# ECG_v2_2.net
KiCad netlist of a schematic drawn in EAGLE
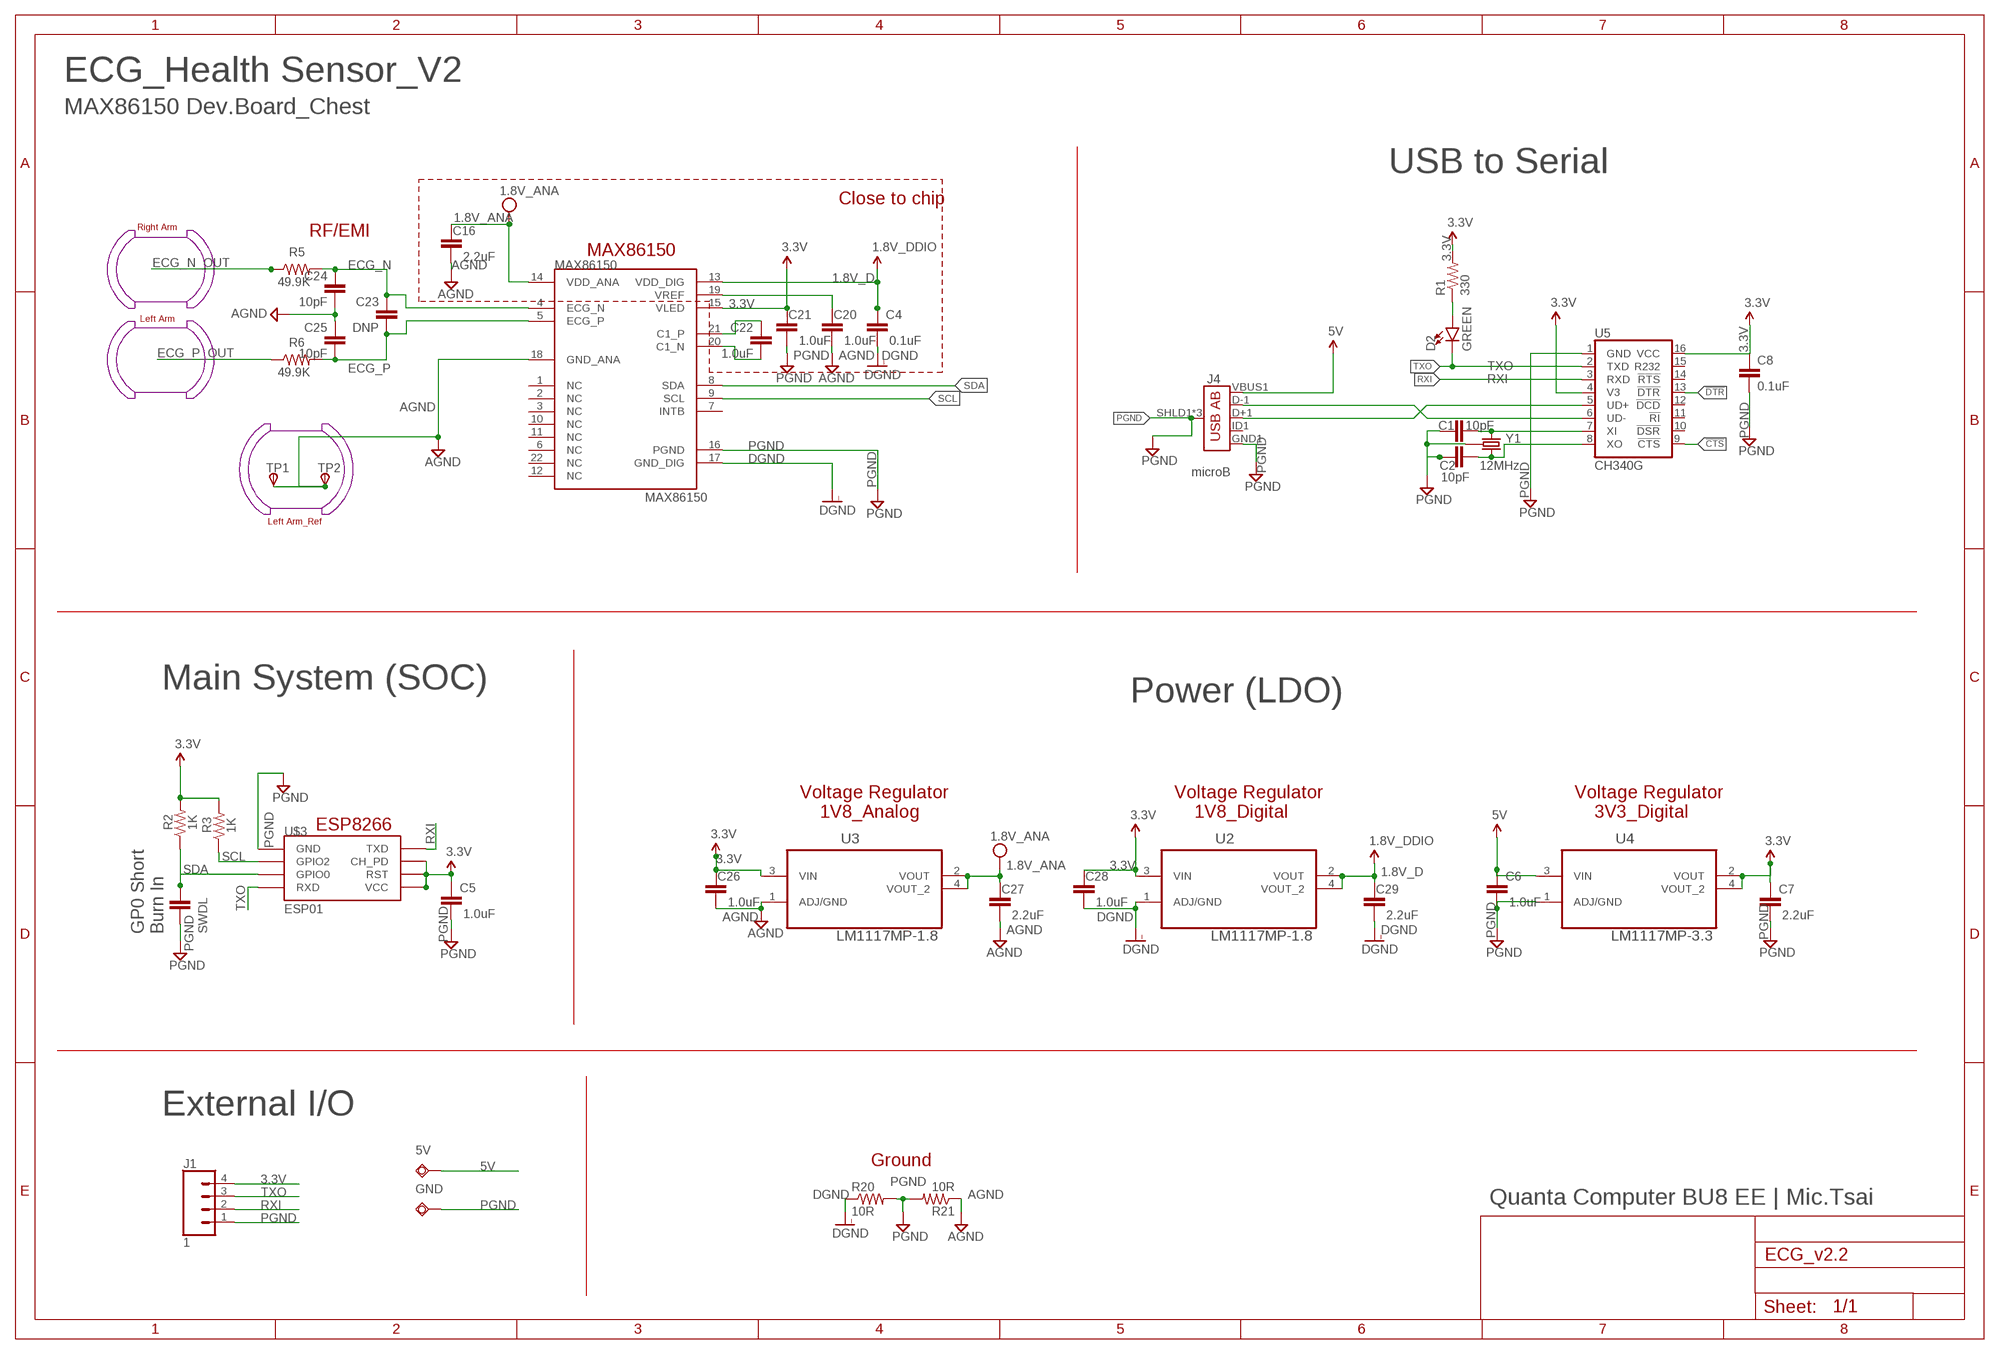
[diagram p0: schematic, sheet 1]

(export (version "E")
  (design (tool "Eeschema 10.0.6"))
  (components
    (comp (ref "5V")
      (value "TPSQTP20R")
      (footprint "eagle-import:TP20R")
      (libsource (lib "eagle-import") (part "TPSQTP20R"))
    )
    (comp (ref "C1")
      (value "10pF")
      (footprint "eagle-import:0603-CAP")
      (libsource (lib "eagle-import") (part "10PF-50V-5%(0603)"))
    )
    (comp (ref "C2")
      (value "10pF")
      (footprint "eagle-import:0603-CAP")
      (libsource (lib "eagle-import") (part "10PF-50V-5%(0603)"))
    )
    (comp (ref "C4")
      (value "0.1uF")
      (footprint "eagle-import:0805")
      (libsource (lib "eagle-import") (part "1.0UF-0805-25V-10%"))
    )
    (comp (ref "C5")
      (value "1.0uF")
      (footprint "eagle-import:0805")
      (libsource (lib "eagle-import") (part "1.0UF-0805-25V-10%"))
    )
    (comp (ref "C6")
      (value "1.0uF")
      (footprint "eagle-import:0805")
      (libsource (lib "eagle-import") (part "1.0UF-0805-25V-10%"))
    )
    (comp (ref "C7")
      (value "2.2uF")
      (footprint "eagle-import:0805")
      (libsource (lib "eagle-import") (part "1.0UF-0805-25V-10%"))
    )
    (comp (ref "C8")
      (value "0.1uF")
      (footprint "eagle-import:0603-CAP")
      (libsource (lib "eagle-import") (part "0.1UF-25V(+80/-20%)(0603)"))
    )
    (comp (ref "C16")
      (value "2.2uF")
      (footprint "eagle-import:0805")
      (libsource (lib "eagle-import") (part "1.0UF-0805-25V-10%"))
    )
    (comp (ref "C20")
      (value "1.0uF")
      (footprint "eagle-import:0805")
      (libsource (lib "eagle-import") (part "1.0UF-0805-25V-10%"))
    )
    (comp (ref "C21")
      (value "1.0uF")
      (footprint "eagle-import:0805")
      (libsource (lib "eagle-import") (part "1.0UF-0805-25V-10%"))
    )
    (comp (ref "C22")
      (value "1.0uF")
      (footprint "eagle-import:0805")
      (libsource (lib "eagle-import") (part "1.0UF-0805-25V-10%"))
    )
    (comp (ref "C23")
      (value "DNP")
      (footprint "eagle-import:0402")
      (libsource (lib "eagle-import") (part "1.0UF-0402-16V-10%"))
    )
    (comp (ref "C24")
      (value "10pF")
      (footprint "eagle-import:0402")
      (libsource (lib "eagle-import") (part "1.0UF-0402-16V-10%"))
    )
    (comp (ref "C25")
      (value "10pF")
      (footprint "eagle-import:0402")
      (libsource (lib "eagle-import") (part "1.0UF-0402-16V-10%"))
    )
    (comp (ref "C26")
      (value "1.0uF")
      (footprint "eagle-import:0805")
      (libsource (lib "eagle-import") (part "1.0UF-0805-25V-10%"))
    )
    (comp (ref "C27")
      (value "2.2uF")
      (footprint "eagle-import:0805")
      (libsource (lib "eagle-import") (part "1.0UF-0805-25V-10%"))
    )
    (comp (ref "C28")
      (value "1.0uF")
      (footprint "eagle-import:0805")
      (libsource (lib "eagle-import") (part "1.0UF-0805-25V-10%"))
    )
    (comp (ref "C29")
      (value "2.2uF")
      (footprint "eagle-import:0805")
      (libsource (lib "eagle-import") (part "1.0UF-0805-25V-10%"))
    )
    (comp (ref "D2")
      (value "GREEN")
      (footprint "eagle-import:LED-0603")
      (libsource (lib "eagle-import") (part "LED-GREEN0603"))
    )
    (comp (ref "GND")
      (value "TPSQTP20R")
      (footprint "eagle-import:TP20R")
      (libsource (lib "eagle-import") (part "TPSQTP20R"))
    )
    (comp (ref "J1")
      (value "1")
      (footprint "eagle-import:1X04")
      (libsource (lib "eagle-import") (part "CONN_04"))
    )
    (comp (ref "J4")
      (value "microB")
      (footprint "eagle-import:USB-AB-MICRO-SMD")
      (libsource (lib "eagle-import") (part "USB_AB_SMT"))
    )
    (comp (ref "MAX86150")
      (value "MAX86150")
      (footprint "eagle-import:MAX86150")
      (libsource (lib "eagle-import") (part "MAX86150"))
    )
    (comp (ref "R1")
      (value "330")
      (footprint "eagle-import:0603-RES")
      (libsource (lib "eagle-import") (part "330OHM1/10W1%(0603)"))
    )
    (comp (ref "R2")
      (value "1K")
      (footprint "eagle-import:0805")
      (libsource (lib "eagle-import") (part "RESISTOR0805-RES"))
    )
    (comp (ref "R3")
      (value "1K")
      (footprint "eagle-import:0805")
      (libsource (lib "eagle-import") (part "RESISTOR0805-RES"))
    )
    (comp (ref "R5")
      (value "49.9K")
      (footprint "eagle-import:0805")
      (libsource (lib "eagle-import") (part "RESISTOR0805-RES"))
    )
    (comp (ref "R6")
      (value "49.9K")
      (footprint "eagle-import:0805")
      (libsource (lib "eagle-import") (part "RESISTOR0805-RES"))
    )
    (comp (ref "R20")
      (value "10R")
      (footprint "eagle-import:0805")
      (libsource (lib "eagle-import") (part "RESISTOR0805-RES"))
    )
    (comp (ref "R21")
      (value "10R")
      (footprint "eagle-import:0805")
      (libsource (lib "eagle-import") (part "RESISTOR0805-RES"))
    )
    (comp (ref "SWDL")
      (value "10pF")
      (footprint "eagle-import:0402")
      (libsource (lib "eagle-import") (part "1.0UF-0402-16V-10%"))
    )
    (comp (ref "TP1")
      (value "TPSB1,27")
      (footprint "eagle-import:B1,27")
      (libsource (lib "eagle-import") (part "TPSB1,27"))
    )
    (comp (ref "TP2")
      (value "TPSB1,27")
      (footprint "eagle-import:B1,27")
      (libsource (lib "eagle-import") (part "TPSB1,27"))
    )
    (comp (ref "U$3")
      (value "ESP01")
      (footprint "eagle-import:ESP01")
      (libsource (lib "eagle-import") (part "ESP01"))
    )
    (comp (ref "U2")
      (value "LM1117MP-1.8")
      (footprint "eagle-import:SOT230P696X180-4N")
      (fields (field (name "MF") "Texas Instruments") (field (name "MP") "LM1117MP-1.8/NOPB"))
      (libsource (lib "eagle-import") (part "LM1117MP-1.8"))
    )
    (comp (ref "U3")
      (value "LM1117MP-1.8")
      (footprint "eagle-import:SOT230P696X180-4N")
      (fields (field (name "MF") "Texas Instruments") (field (name "MP") "LM1117MP-1.8/NOPB"))
      (libsource (lib "eagle-import") (part "LM1117MP-1.8"))
    )
    (comp (ref "U4")
      (value "LM1117MP-3.3")
      (footprint "eagle-import:SOT230P696X180-4N")
      (fields (field (name "MF") "Texas Instruments") (field (name "MP") "LM1117MP-1.8/NOPB"))
      (libsource (lib "eagle-import") (part "LM1117MP-3.3"))
    )
    (comp (ref "U5")
      (value "CH340G")
      (footprint "eagle-import:SO016")
      (libsource (lib "eagle-import") (part "CH340GSMD"))
    )
    (comp (ref "Y1")
      (value "12MHz")
      (footprint "eagle-import:CRYSTAL-SMD-3.2X2.5")
      (libsource (lib "eagle-import") (part "CRYSTAL-GROUNDED3.2X2.5"))
    )
  )
  (nets
    (net (code "1") (name "/ECG_N") (class "Default")
      (node (ref "C23") (pin "1") (pinfunction "1_1") (pintype "passive"))
      (node (ref "C24") (pin "1") (pinfunction "1_1") (pintype "passive"))
      (node (ref "MAX86150") (pin "4") (pinfunction "ECG_N_4") (pintype "bidirectional"))
      (node (ref "R5") (pin "2") (pinfunction "2_2") (pintype "passive"))
    )
    (net (code "2") (name "/ECG_N_OUT") (class "Default")
      (node (ref "R5") (pin "1") (pinfunction "1_1") (pintype "passive"))
    )
    (net (code "3") (name "/ECG_P") (class "Default")
      (node (ref "C23") (pin "2") (pinfunction "2_2") (pintype "passive"))
      (node (ref "C25") (pin "2") (pinfunction "2_2") (pintype "passive"))
      (node (ref "MAX86150") (pin "5") (pinfunction "ECG_P_5") (pintype "bidirectional"))
      (node (ref "R6") (pin "2") (pinfunction "2_2") (pintype "passive"))
    )
    (net (code "4") (name "/ECG_P_OUT") (class "Default")
      (node (ref "R6") (pin "1") (pinfunction "1_1") (pintype "passive"))
    )
    (net (code "5") (name "/~{CTS}") (class "Default")
      (node (ref "U5") (pin "9") (pinfunction "~{CTS}_9") (pintype "bidirectional"))
    )
    (net (code "6") (name "/~{DTR}") (class "Default")
      (node (ref "U5") (pin "13") (pinfunction "~{DTR}_13") (pintype "bidirectional"))
    )
    (net (code "7") (name "1.8V_ANA") (class "Default")
      (node (ref "C16") (pin "1") (pinfunction "1_1") (pintype "passive"))
      (node (ref "C27") (pin "1") (pinfunction "1_1") (pintype "passive"))
      (node (ref "MAX86150") (pin "14") (pinfunction "VDD_ANA_14") (pintype "bidirectional"))
      (node (ref "U3") (pin "2") (pinfunction "VOUT_2") (pintype "output"))
      (node (ref "U3") (pin "4") (pinfunction "VOUT_2_4") (pintype "output"))
    )
    (net (code "8") (name "1.8V_DDIO") (class "Default")
      (node (ref "C29") (pin "1") (pinfunction "1_1") (pintype "passive"))
      (node (ref "C4") (pin "1") (pinfunction "1_1") (pintype "passive"))
      (node (ref "MAX86150") (pin "13") (pinfunction "VDD_DIG_13") (pintype "bidirectional"))
      (node (ref "U2") (pin "2") (pinfunction "VOUT_2") (pintype "output"))
      (node (ref "U2") (pin "4") (pinfunction "VOUT_2_4") (pintype "output"))
    )
    (net (code "9") (name "3.3V") (class "Default")
      (node (ref "C21") (pin "1") (pinfunction "1_1") (pintype "passive"))
      (node (ref "C26") (pin "1") (pinfunction "1_1") (pintype "passive"))
      (node (ref "C28") (pin "1") (pinfunction "1_1") (pintype "passive"))
      (node (ref "C5") (pin "1") (pinfunction "1_1") (pintype "passive"))
      (node (ref "C7") (pin "1") (pinfunction "1_1") (pintype "passive"))
      (node (ref "C8") (pin "1") (pinfunction "1_1") (pintype "passive"))
      (node (ref "J1") (pin "4") (pinfunction "4_4") (pintype "passive"))
      (node (ref "MAX86150") (pin "15") (pinfunction "VLED_15") (pintype "bidirectional"))
      (node (ref "R1") (pin "2") (pinfunction "2_2") (pintype "passive"))
      (node (ref "R2") (pin "2") (pinfunction "2_2") (pintype "passive"))
      (node (ref "R3") (pin "2") (pinfunction "2_2") (pintype "passive"))
      (node (ref "U$3") (pin "CH_PD") (pinfunction "CH_PD_CH_PD") (pintype "bidirectional"))
      (node (ref "U$3") (pin "RST") (pinfunction "RST_RST") (pintype "bidirectional"))
      (node (ref "U$3") (pin "VCC") (pinfunction "VCC_VCC") (pintype "bidirectional"))
      (node (ref "U2") (pin "3") (pinfunction "VIN_3") (pintype "input"))
      (node (ref "U3") (pin "3") (pinfunction "VIN_3") (pintype "input"))
      (node (ref "U4") (pin "2") (pinfunction "VOUT_2") (pintype "output"))
      (node (ref "U4") (pin "4") (pinfunction "VOUT_2_4") (pintype "output"))
      (node (ref "U5") (pin "16") (pinfunction "VCC_16") (pintype "bidirectional"))
      (node (ref "U5") (pin "4") (pinfunction "V3_4") (pintype "bidirectional"))
    )
    (net (code "10") (name "5V") (class "Default")
      (node (ref "5V") (pin "TP") (pinfunction "TP_TP") (pintype "input"))
      (node (ref "C6") (pin "1") (pinfunction "1_1") (pintype "passive"))
      (node (ref "J4") (pin "VBUS1") (pinfunction "VBUS_VBUS1") (pintype "power_in"))
      (node (ref "U4") (pin "3") (pinfunction "VIN_3") (pintype "input"))
    )
    (net (code "11") (name "AGND") (class "Default")
      (node (ref "C16") (pin "2") (pinfunction "2_2") (pintype "passive"))
      (node (ref "C20") (pin "2") (pinfunction "2_2") (pintype "passive"))
      (node (ref "C24") (pin "2") (pinfunction "2_2") (pintype "passive"))
      (node (ref "C25") (pin "1") (pinfunction "1_1") (pintype "passive"))
      (node (ref "C26") (pin "2") (pinfunction "2_2") (pintype "passive"))
      (node (ref "C27") (pin "2") (pinfunction "2_2") (pintype "passive"))
      (node (ref "MAX86150") (pin "18") (pinfunction "GND_ANA_18") (pintype "bidirectional"))
      (node (ref "R21") (pin "1") (pinfunction "1_1") (pintype "passive"))
      (node (ref "TP1") (pin "PP") (pinfunction "PP_PP") (pintype "input"))
      (node (ref "TP2") (pin "PP") (pinfunction "PP_PP") (pintype "input"))
      (node (ref "U3") (pin "1") (pinfunction "ADJ/GND_1") (pintype "passive"))
    )
    (net (code "12") (name "DGND") (class "Default")
      (node (ref "C28") (pin "2") (pinfunction "2_2") (pintype "passive"))
      (node (ref "C29") (pin "2") (pinfunction "2_2") (pintype "passive"))
      (node (ref "C4") (pin "2") (pinfunction "2_2") (pintype "passive"))
      (node (ref "MAX86150") (pin "17") (pinfunction "GND_DIG_17") (pintype "bidirectional"))
      (node (ref "R20") (pin "1") (pinfunction "1_1") (pintype "passive"))
      (node (ref "U2") (pin "1") (pinfunction "ADJ/GND_1") (pintype "passive"))
    )
    (net (code "13") (name "Net-(D2-PadA)") (class "Default")
      (node (ref "D2") (pin "A") (pinfunction "A_A") (pintype "passive"))
      (node (ref "R1") (pin "1") (pinfunction "1_1") (pintype "passive"))
    )
    (net (code "14") (name "Net-(J4-D+)") (class "Default")
      (node (ref "J4") (pin "D+1") (pinfunction "D+_D+1") (pintype "bidirectional"))
      (node (ref "U5") (pin "5") (pinfunction "UD+_5") (pintype "bidirectional"))
    )
    (net (code "15") (name "Net-(J4-D-)") (class "Default")
      (node (ref "J4") (pin "D-1") (pinfunction "D-_D-1") (pintype "bidirectional"))
      (node (ref "U5") (pin "6") (pinfunction "UD-_6") (pintype "bidirectional"))
    )
    (net (code "16") (name "Net-(MAX86150-C1_N)") (class "Default")
      (node (ref "C22") (pin "2") (pinfunction "2_2") (pintype "passive"))
      (node (ref "MAX86150") (pin "20") (pinfunction "C1_N_20") (pintype "bidirectional"))
    )
    (net (code "17") (name "Net-(MAX86150-C1_P)") (class "Default")
      (node (ref "C22") (pin "1") (pinfunction "1_1") (pintype "passive"))
      (node (ref "MAX86150") (pin "21") (pinfunction "C1_P_21") (pintype "bidirectional"))
    )
    (net (code "18") (name "Net-(MAX86150-VREF)") (class "Default")
      (node (ref "C20") (pin "1") (pinfunction "1_1") (pintype "passive"))
      (node (ref "MAX86150") (pin "19") (pinfunction "VREF_19") (pintype "bidirectional"))
    )
    (net (code "19") (name "Net-(U5-XI)") (class "Default")
      (node (ref "C1") (pin "2") (pinfunction "2_2") (pintype "passive"))
      (node (ref "U5") (pin "7") (pinfunction "XI_7") (pintype "bidirectional"))
      (node (ref "Y1") (pin "1") (pinfunction "1_1") (pintype "passive"))
    )
    (net (code "20") (name "Net-(U5-XO)") (class "Default")
      (node (ref "C2") (pin "2") (pinfunction "2_2") (pintype "passive"))
      (node (ref "U5") (pin "8") (pinfunction "XO_8") (pintype "bidirectional"))
      (node (ref "Y1") (pin "3") (pinfunction "2_3") (pintype "passive"))
    )
    (net (code "21") (name "PGND") (class "Default")
      (node (ref "C1") (pin "1") (pinfunction "1_1") (pintype "passive"))
      (node (ref "C2") (pin "1") (pinfunction "1_1") (pintype "passive"))
      (node (ref "C21") (pin "2") (pinfunction "2_2") (pintype "passive"))
      (node (ref "C5") (pin "2") (pinfunction "2_2") (pintype "passive"))
      (node (ref "C6") (pin "2") (pinfunction "2_2") (pintype "passive"))
      (node (ref "C7") (pin "2") (pinfunction "2_2") (pintype "passive"))
      (node (ref "C8") (pin "2") (pinfunction "2_2") (pintype "passive"))
      (node (ref "GND") (pin "TP") (pinfunction "TP_TP") (pintype "input"))
      (node (ref "J1") (pin "1") (pinfunction "1_1") (pintype "passive"))
      (node (ref "J4") (pin "GND1") (pinfunction "GND_GND1") (pintype "power_in"))
      (node (ref "J4") (pin "SHLD1") (pinfunction "SHIELD_SHLD1") (pintype "bidirectional"))
      (node (ref "J4") (pin "SHLD2") (pinfunction "SHIELD_SHLD2") (pintype "bidirectional"))
      (node (ref "J4") (pin "SHLD3") (pinfunction "SHIELD_SHLD3") (pintype "bidirectional"))
      (node (ref "MAX86150") (pin "16") (pinfunction "PGND_16") (pintype "bidirectional"))
      (node (ref "R20") (pin "2") (pinfunction "2_2") (pintype "passive"))
      (node (ref "R21") (pin "2") (pinfunction "2_2") (pintype "passive"))
      (node (ref "SWDL") (pin "2") (pinfunction "2_2") (pintype "passive"))
      (node (ref "U$3") (pin "GND") (pinfunction "GND_GND") (pintype "bidirectional"))
      (node (ref "U4") (pin "1") (pinfunction "ADJ/GND_1") (pintype "passive"))
      (node (ref "U5") (pin "1") (pinfunction "GND_1") (pintype "bidirectional"))
      (node (ref "Y1") (pin "2") (pinfunction "GND_2") (pintype "passive"))
      (node (ref "Y1") (pin "4") (pinfunction "GND_4") (pintype "passive"))
    )
    (net (code "22") (name "RXI") (class "Default")
      (node (ref "J1") (pin "2") (pinfunction "2_2") (pintype "passive"))
      (node (ref "U$3") (pin "TX") (pinfunction "TXD_TX") (pintype "bidirectional"))
      (node (ref "U5") (pin "3") (pinfunction "RXD_3") (pintype "bidirectional"))
    )
    (net (code "23") (name "SCL") (class "Default")
      (node (ref "MAX86150") (pin "9") (pinfunction "SCL_9") (pintype "bidirectional"))
      (node (ref "R3") (pin "1") (pinfunction "1_1") (pintype "passive"))
      (node (ref "U$3") (pin "GPIO2") (pinfunction "GPIO2_GPIO2") (pintype "bidirectional"))
    )
    (net (code "24") (name "SDA") (class "Default")
      (node (ref "MAX86150") (pin "8") (pinfunction "SDA_8") (pintype "bidirectional"))
      (node (ref "R2") (pin "1") (pinfunction "1_1") (pintype "passive"))
      (node (ref "SWDL") (pin "1") (pinfunction "1_1") (pintype "passive"))
      (node (ref "U$3") (pin "GPIO0") (pinfunction "GPIO0_GPIO0") (pintype "bidirectional"))
    )
    (net (code "25") (name "TXO") (class "Default")
      (node (ref "D2") (pin "C") (pinfunction "C_C") (pintype "passive"))
      (node (ref "J1") (pin "3") (pinfunction "3_3") (pintype "passive"))
      (node (ref "U$3") (pin "RX") (pinfunction "RXD_RX") (pintype "bidirectional"))
      (node (ref "U5") (pin "2") (pinfunction "TXD_2") (pintype "bidirectional"))
    )
    (net (code "26") (name "unconnected-(J4-USBID-PadID1)") (class "Default")
      (node (ref "J4") (pin "ID1") (pinfunction "USBID_ID1") (pintype "bidirectional"))
    )
    (net (code "27") (name "unconnected-(MAX86150-INTB-Pad7)") (class "Default")
      (node (ref "MAX86150") (pin "7") (pinfunction "INTB_7") (pintype "bidirectional"))
    )
    (net (code "28") (name "unconnected-(MAX86150-NC-Pad1)") (class "Default")
      (node (ref "MAX86150") (pin "1") (pinfunction "NC_1") (pintype "bidirectional"))
    )
    (net (code "29") (name "unconnected-(MAX86150-NC-Pad2)") (class "Default")
      (node (ref "MAX86150") (pin "2") (pinfunction "NC_2") (pintype "bidirectional"))
    )
    (net (code "30") (name "unconnected-(MAX86150-NC-Pad3)") (class "Default")
      (node (ref "MAX86150") (pin "3") (pinfunction "NC_3") (pintype "bidirectional"))
    )
    (net (code "31") (name "unconnected-(MAX86150-NC-Pad6)") (class "Default")
      (node (ref "MAX86150") (pin "6") (pinfunction "NC_6") (pintype "bidirectional"))
    )
    (net (code "32") (name "unconnected-(MAX86150-NC-Pad10)") (class "Default")
      (node (ref "MAX86150") (pin "10") (pinfunction "NC_10") (pintype "bidirectional"))
    )
    (net (code "33") (name "unconnected-(MAX86150-NC-Pad11)") (class "Default")
      (node (ref "MAX86150") (pin "11") (pinfunction "NC_11") (pintype "bidirectional"))
    )
    (net (code "34") (name "unconnected-(MAX86150-NC-Pad12)") (class "Default")
      (node (ref "MAX86150") (pin "12") (pinfunction "NC_12") (pintype "bidirectional"))
    )
    (net (code "35") (name "unconnected-(MAX86150-NC-Pad22)") (class "Default")
      (node (ref "MAX86150") (pin "22") (pinfunction "NC_22") (pintype "bidirectional"))
    )
    (net (code "36") (name "unconnected-(U5-R232-Pad15)") (class "Default")
      (node (ref "U5") (pin "15") (pinfunction "R232_15") (pintype "bidirectional"))
    )
    (net (code "37") (name "unconnected-(U5-~{DCD}-Pad12)") (class "Default")
      (node (ref "U5") (pin "12") (pinfunction "~{DCD}_12") (pintype "bidirectional"))
    )
    (net (code "38") (name "unconnected-(U5-~{DSR}-Pad10)") (class "Default")
      (node (ref "U5") (pin "10") (pinfunction "~{DSR}_10") (pintype "bidirectional"))
    )
    (net (code "39") (name "unconnected-(U5-~{RI}-Pad11)") (class "Default")
      (node (ref "U5") (pin "11") (pinfunction "~{RI}_11") (pintype "bidirectional"))
    )
    (net (code "40") (name "unconnected-(U5-~{RTS}-Pad14)") (class "Default")
      (node (ref "U5") (pin "14") (pinfunction "~{RTS}_14") (pintype "bidirectional"))
    )
  )
)
